# MODUL_LCD_V100.net
KiCad netlist of a schematic drawn in EAGLE
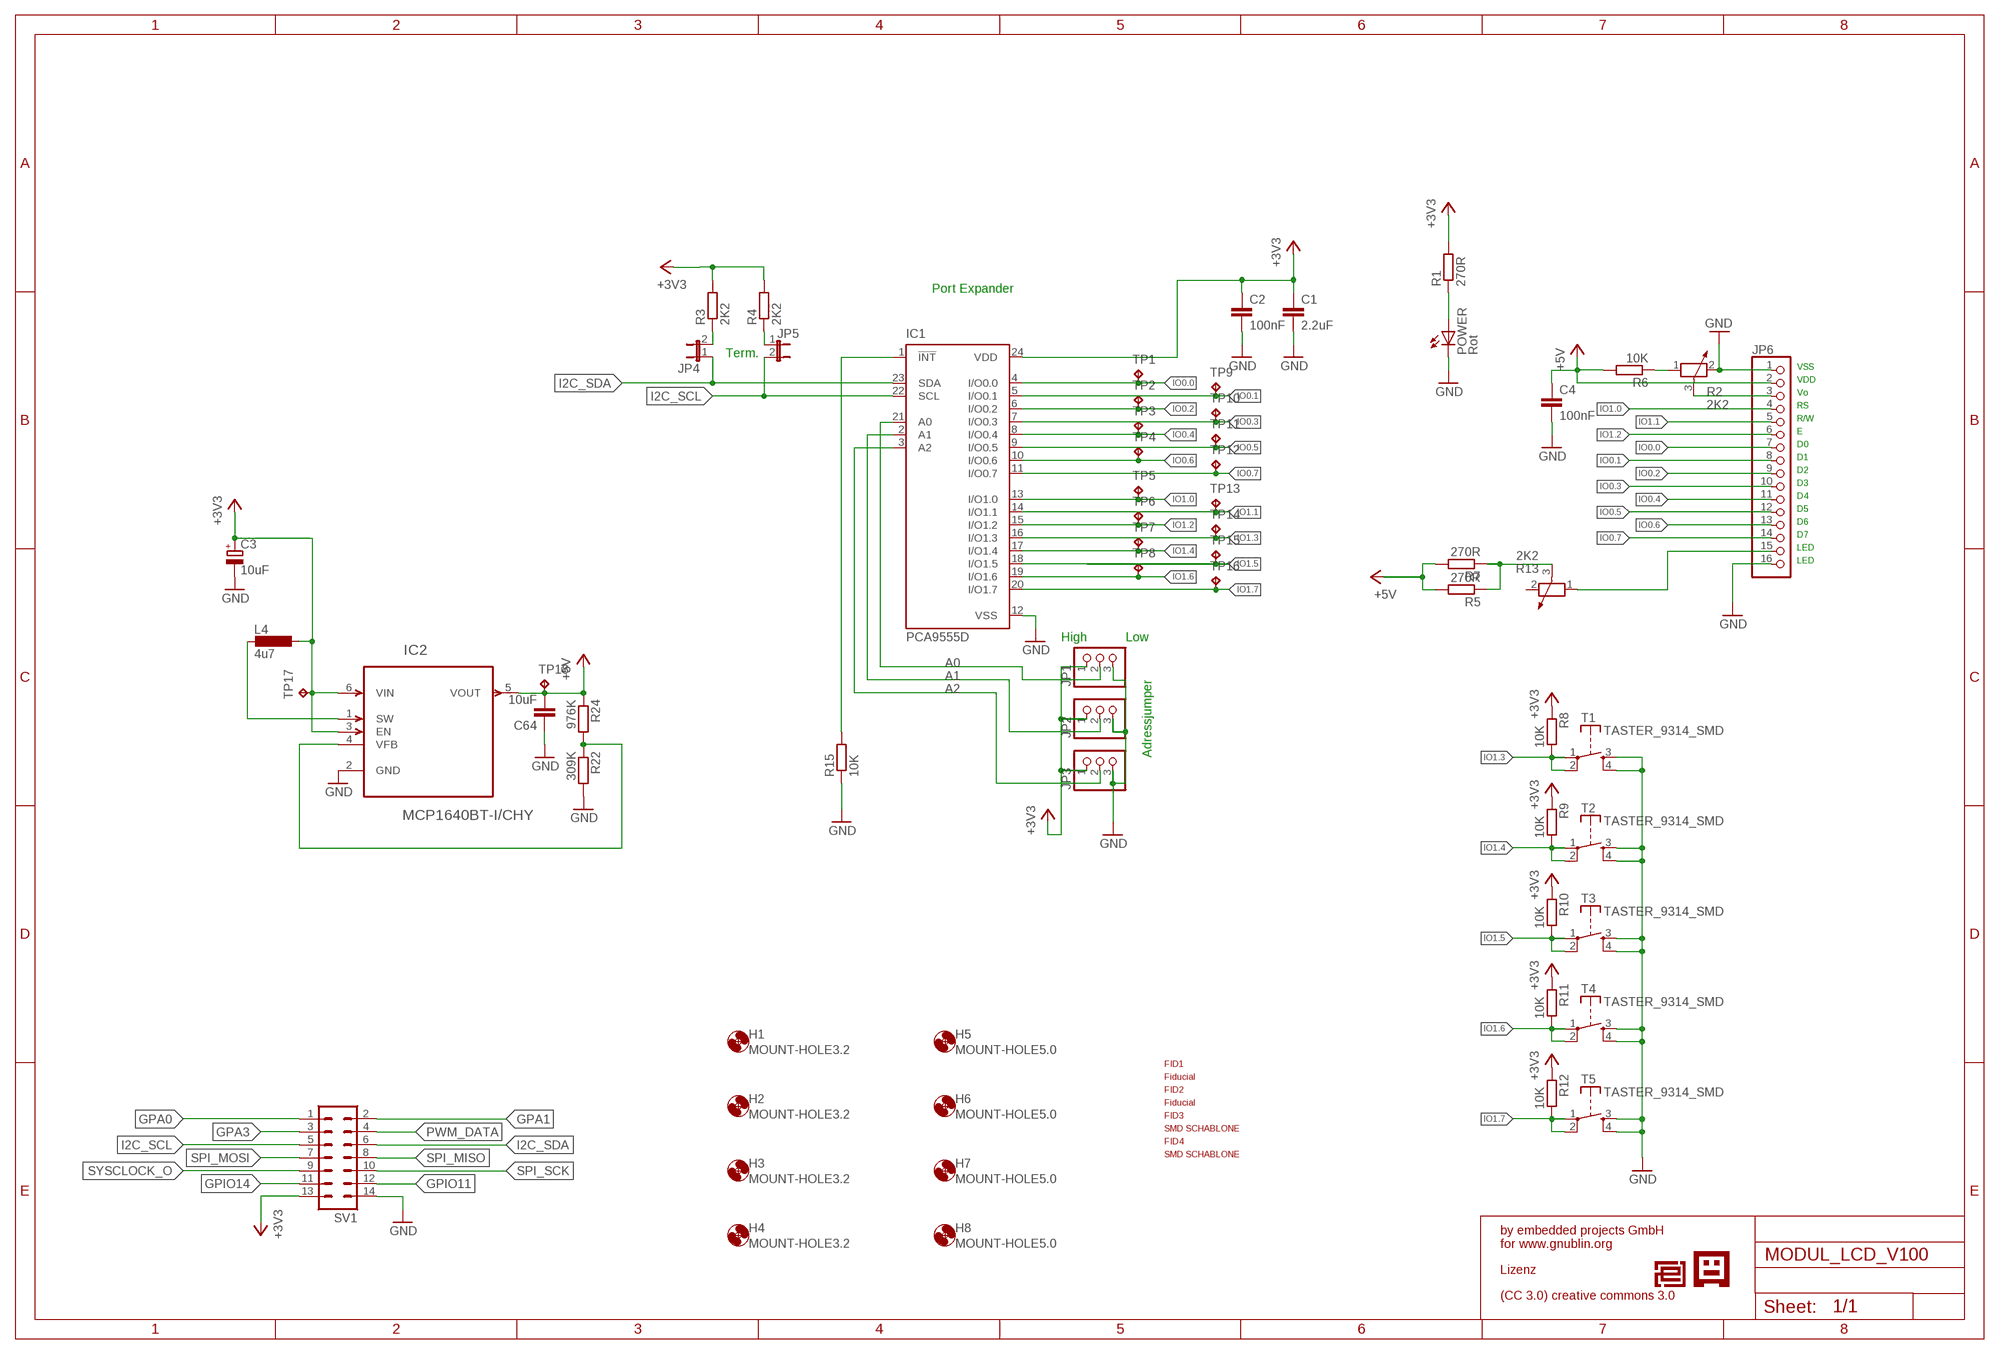
[diagram p0: schematic, sheet 1]

(export (version "E")
  (design (tool "Eeschema 10.0.6"))
  (components
    (comp (ref "C1")
      (value "2.2uF")
      (footprint "eagle-import:C0805")
      (libsource (lib "eagle-import") (part "C-EUC0805"))
    )
    (comp (ref "C2")
      (value "100nF")
      (footprint "eagle-import:C0805")
      (libsource (lib "eagle-import") (part "C-EUC0805"))
    )
    (comp (ref "C3")
      (value "10uF")
      (footprint "eagle-import:SMC_D")
      (libsource (lib "eagle-import") (part "CPOL-EUSMCD"))
    )
    (comp (ref "C4")
      (value "100nF")
      (footprint "eagle-import:C0805")
      (libsource (lib "eagle-import") (part "C-EUC0805"))
    )
    (comp (ref "C64")
      (value "10uF")
      (footprint "eagle-import:C0805")
      (libsource (lib "eagle-import") (part "C-EUC0805"))
    )
    (comp (ref "FID1")
      (value "PASSERMARKEN_FIDUCIAL")
      (footprint "eagle-import:PASSERMARKEN_FIDUCIAL")
      (libsource (lib "eagle-import") (part "PASSERMARKEN_FIDUCIAL"))
    )
    (comp (ref "FID2")
      (value "PASSERMARKEN_FIDUCIAL")
      (footprint "eagle-import:PASSERMARKEN_FIDUCIAL")
      (libsource (lib "eagle-import") (part "PASSERMARKEN_FIDUCIAL"))
    )
    (comp (ref "FID3")
      (value "PASSERMARKEN_FIDUCIAL")
      (footprint "eagle-import:PASSERMARKEN_FIDUCIAL")
      (libsource (lib "eagle-import") (part "SMDSCHABLONE_PASSERMARKEN_FIDUCIAL"))
    )
    (comp (ref "FID4")
      (value "PASSERMARKEN_FIDUCIAL")
      (footprint "eagle-import:PASSERMARKEN_FIDUCIAL")
      (libsource (lib "eagle-import") (part "SMDSCHABLONE_PASSERMARKEN_FIDUCIAL"))
    )
    (comp (ref "H1")
      (value "MOUNT-HOLE3.2")
      (footprint "eagle-import:3,2")
      (libsource (lib "eagle-import") (part "MOUNT-HOLE3.2"))
    )
    (comp (ref "H2")
      (value "MOUNT-HOLE3.2")
      (footprint "eagle-import:3,2")
      (libsource (lib "eagle-import") (part "MOUNT-HOLE3.2"))
    )
    (comp (ref "H3")
      (value "MOUNT-HOLE3.2")
      (footprint "eagle-import:3,2")
      (libsource (lib "eagle-import") (part "MOUNT-HOLE3.2"))
    )
    (comp (ref "H4")
      (value "MOUNT-HOLE3.2")
      (footprint "eagle-import:3,2")
      (libsource (lib "eagle-import") (part "MOUNT-HOLE3.2"))
    )
    (comp (ref "H5")
      (value "MOUNT-HOLE5.0")
      (footprint "eagle-import:5,0")
      (libsource (lib "eagle-import") (part "MOUNT-HOLE5.0"))
    )
    (comp (ref "H6")
      (value "MOUNT-HOLE5.0")
      (footprint "eagle-import:5,0")
      (libsource (lib "eagle-import") (part "MOUNT-HOLE5.0"))
    )
    (comp (ref "H7")
      (value "MOUNT-HOLE5.0")
      (footprint "eagle-import:5,0")
      (libsource (lib "eagle-import") (part "MOUNT-HOLE5.0"))
    )
    (comp (ref "H8")
      (value "MOUNT-HOLE5.0")
      (footprint "eagle-import:5,0")
      (libsource (lib "eagle-import") (part "MOUNT-HOLE5.0"))
    )
    (comp (ref "IC1")
      (value "PCA9555D")
      (footprint "eagle-import:SO24")
      (fields (field (name "MPN") "PCA9555DW") (field (name "OC_FARNELL") "8906076"))
      (libsource (lib "eagle-import") (part "PCA9555D"))
    )
    (comp (ref "IC2")
      (value "MCP1640BT-I/CHY")
      (footprint "eagle-import:SOT95P270X145-6N")
      (libsource (lib "eagle-import") (part "MCP1640BT-I/CHY"))
    )
    (comp (ref "JP1")
      (value "PINHD-1X3")
      (footprint "eagle-import:1X03")
      (libsource (lib "eagle-import") (part "PINHD-1X3"))
    )
    (comp (ref "JP2")
      (value "PINHD-1X3")
      (footprint "eagle-import:1X03")
      (libsource (lib "eagle-import") (part "PINHD-1X3"))
    )
    (comp (ref "JP3")
      (value "PINHD-1X3")
      (footprint "eagle-import:1X03")
      (libsource (lib "eagle-import") (part "PINHD-1X3"))
    )
    (comp (ref "JP4")
      (value "JP1E")
      (footprint "eagle-import:JP1")
      (libsource (lib "eagle-import") (part "JP1E"))
    )
    (comp (ref "JP5")
      (value "JP1E")
      (footprint "eagle-import:JP1")
      (libsource (lib "eagle-import") (part "JP1E"))
    )
    (comp (ref "JP6")
      (value "PINHD-1X16")
      (footprint "eagle-import:1X16")
      (libsource (lib "eagle-import") (part "PINHD-1X16"))
    )
    (comp (ref "L4")
      (value "4u7")
      (footprint "eagle-import:PSU3014")
      (libsource (lib "eagle-import") (part "PSU3014"))
    )
    (comp (ref "POWER")
      (value "Rot")
      (footprint "eagle-import:CHIP-LED0805")
      (libsource (lib "eagle-import") (part "LEDCHIP-LED0805"))
    )
    (comp (ref "R1")
      (value "270R")
      (footprint "eagle-import:R0805")
      (libsource (lib "eagle-import") (part "R-EU_R0805"))
    )
    (comp (ref "R2")
      (value "2K2")
      (footprint "eagle-import:PT-10")
      (libsource (lib "eagle-import") (part "POTENTIOMETER_PT-10"))
    )
    (comp (ref "R3")
      (value "2K2")
      (footprint "eagle-import:R0805")
      (libsource (lib "eagle-import") (part "R-EU_R0805"))
    )
    (comp (ref "R4")
      (value "2K2")
      (footprint "eagle-import:R0805")
      (libsource (lib "eagle-import") (part "R-EU_R0805"))
    )
    (comp (ref "R5")
      (value "270R")
      (footprint "eagle-import:R0805")
      (libsource (lib "eagle-import") (part "R-EU_R0805"))
    )
    (comp (ref "R6")
      (value "10K")
      (footprint "eagle-import:R0805")
      (libsource (lib "eagle-import") (part "R-EU_R0805"))
    )
    (comp (ref "R7")
      (value "270R")
      (footprint "eagle-import:R0805")
      (libsource (lib "eagle-import") (part "R-EU_R0805"))
    )
    (comp (ref "R8")
      (value "10K")
      (footprint "eagle-import:R0805")
      (libsource (lib "eagle-import") (part "R-EU_R0805"))
    )
    (comp (ref "R9")
      (value "10K")
      (footprint "eagle-import:R0805")
      (libsource (lib "eagle-import") (part "R-EU_R0805"))
    )
    (comp (ref "R10")
      (value "10K")
      (footprint "eagle-import:R0805")
      (libsource (lib "eagle-import") (part "R-EU_R0805"))
    )
    (comp (ref "R11")
      (value "10K")
      (footprint "eagle-import:R0805")
      (libsource (lib "eagle-import") (part "R-EU_R0805"))
    )
    (comp (ref "R12")
      (value "10K")
      (footprint "eagle-import:R0805")
      (libsource (lib "eagle-import") (part "R-EU_R0805"))
    )
    (comp (ref "R13")
      (value "2K2")
      (footprint "eagle-import:PT-10")
      (libsource (lib "eagle-import") (part "POTENTIOMETER_PT-10"))
    )
    (comp (ref "R15")
      (value "10K")
      (footprint "eagle-import:R0805")
      (libsource (lib "eagle-import") (part "R-EU_R0805"))
    )
    (comp (ref "R22")
      (value "309K")
      (footprint "eagle-import:R0805")
      (libsource (lib "eagle-import") (part "R-EU_R0805"))
    )
    (comp (ref "R24")
      (value "976K")
      (footprint "eagle-import:R0805")
      (libsource (lib "eagle-import") (part "R-EU_R0805"))
    )
    (comp (ref "SV1")
      (value "ML14")
      (footprint "eagle-import:ML14")
      (libsource (lib "eagle-import") (part "ML14"))
    )
    (comp (ref "T1")
      (value "TASTER_9314_SMD")
      (footprint "eagle-import:TASTER-9314_SMD")
      (libsource (lib "eagle-import") (part "TASTER_9314_SMD"))
    )
    (comp (ref "T2")
      (value "TASTER_9314_SMD")
      (footprint "eagle-import:TASTER-9314_SMD")
      (libsource (lib "eagle-import") (part "TASTER_9314_SMD"))
    )
    (comp (ref "T3")
      (value "TASTER_9314_SMD")
      (footprint "eagle-import:TASTER-9314_SMD")
      (libsource (lib "eagle-import") (part "TASTER_9314_SMD"))
    )
    (comp (ref "T4")
      (value "TASTER_9314_SMD")
      (footprint "eagle-import:TASTER-9314_SMD")
      (libsource (lib "eagle-import") (part "TASTER_9314_SMD"))
    )
    (comp (ref "T5")
      (value "TASTER_9314_SMD")
      (footprint "eagle-import:TASTER-9314_SMD")
      (libsource (lib "eagle-import") (part "TASTER_9314_SMD"))
    )
    (comp (ref "TP1")
      (value "TPB1,27")
      (footprint "eagle-import:B1,27")
      (libsource (lib "eagle-import") (part "TPB1,27"))
    )
    (comp (ref "TP2")
      (value "TPB1,27")
      (footprint "eagle-import:B1,27")
      (libsource (lib "eagle-import") (part "TPB1,27"))
    )
    (comp (ref "TP3")
      (value "TPB1,27")
      (footprint "eagle-import:B1,27")
      (libsource (lib "eagle-import") (part "TPB1,27"))
    )
    (comp (ref "TP4")
      (value "TPB1,27")
      (footprint "eagle-import:B1,27")
      (libsource (lib "eagle-import") (part "TPB1,27"))
    )
    (comp (ref "TP5")
      (value "TPB1,27")
      (footprint "eagle-import:B1,27")
      (libsource (lib "eagle-import") (part "TPB1,27"))
    )
    (comp (ref "TP6")
      (value "TPB1,27")
      (footprint "eagle-import:B1,27")
      (libsource (lib "eagle-import") (part "TPB1,27"))
    )
    (comp (ref "TP7")
      (value "TPB1,27")
      (footprint "eagle-import:B1,27")
      (libsource (lib "eagle-import") (part "TPB1,27"))
    )
    (comp (ref "TP8")
      (value "TPB1,27")
      (footprint "eagle-import:B1,27")
      (libsource (lib "eagle-import") (part "TPB1,27"))
    )
    (comp (ref "TP9")
      (value "TPB1,27")
      (footprint "eagle-import:B1,27")
      (libsource (lib "eagle-import") (part "TPB1,27"))
    )
    (comp (ref "TP10")
      (value "TPB1,27")
      (footprint "eagle-import:B1,27")
      (libsource (lib "eagle-import") (part "TPB1,27"))
    )
    (comp (ref "TP11")
      (value "TPB1,27")
      (footprint "eagle-import:B1,27")
      (libsource (lib "eagle-import") (part "TPB1,27"))
    )
    (comp (ref "TP12")
      (value "TPB1,27")
      (footprint "eagle-import:B1,27")
      (libsource (lib "eagle-import") (part "TPB1,27"))
    )
    (comp (ref "TP13")
      (value "TPB1,27")
      (footprint "eagle-import:B1,27")
      (libsource (lib "eagle-import") (part "TPB1,27"))
    )
    (comp (ref "TP14")
      (value "TPB1,27")
      (footprint "eagle-import:B1,27")
      (libsource (lib "eagle-import") (part "TPB1,27"))
    )
    (comp (ref "TP15")
      (value "TPB1,27")
      (footprint "eagle-import:B1,27")
      (libsource (lib "eagle-import") (part "TPB1,27"))
    )
    (comp (ref "TP16")
      (value "TPB1,27")
      (footprint "eagle-import:B1,27")
      (libsource (lib "eagle-import") (part "TPB1,27"))
    )
    (comp (ref "TP17")
      (value "TPB1,27")
      (footprint "eagle-import:B1,27")
      (libsource (lib "eagle-import") (part "TPB1,27"))
    )
    (comp (ref "TP18")
      (value "TPB1,27")
      (footprint "eagle-import:B1,27")
      (libsource (lib "eagle-import") (part "TPB1,27"))
    )
    (comp (ref "U$1")
      (value "EPLOGOSIEB")
      (footprint "eagle-import:EPLOGOSIEBDRUCK")
      (libsource (lib "eagle-import") (part "EPLOGOSIEB"))
    )
    (comp (ref "U$2")
      (value "GNUBLINLOGOSIEB")
      (footprint "eagle-import:GNUSIEBDRUCK")
      (libsource (lib "eagle-import") (part "GNUBLINLOGOSIEB"))
    )
  )
  (nets
    (net (code "1") (name "+3V3") (class "Default")
      (node (ref "C1") (pin "1") (pinfunction "1_1") (pintype "passive"))
      (node (ref "C2") (pin "1") (pinfunction "1_1") (pintype "passive"))
      (node (ref "C3") (pin "+") (pinfunction "+_+") (pintype "passive"))
      (node (ref "IC1") (pin "24") (pinfunction "VDD_24") (pintype "power_in"))
      (node (ref "IC2") (pin "3") (pinfunction "EN_3") (pintype "input"))
      (node (ref "IC2") (pin "6") (pinfunction "VIN_6") (pintype "input"))
      (node (ref "JP1") (pin "1") (pinfunction "1_1") (pintype "passive"))
      (node (ref "JP2") (pin "1") (pinfunction "1_1") (pintype "passive"))
      (node (ref "JP3") (pin "1") (pinfunction "1_1") (pintype "passive"))
      (node (ref "L4") (pin "2") (pinfunction "2_2") (pintype "passive"))
      (node (ref "R1") (pin "2") (pinfunction "2_2") (pintype "passive"))
      (node (ref "R10") (pin "1") (pinfunction "1_1") (pintype "passive"))
      (node (ref "R11") (pin "1") (pinfunction "1_1") (pintype "passive"))
      (node (ref "R12") (pin "1") (pinfunction "1_1") (pintype "passive"))
      (node (ref "R3") (pin "2") (pinfunction "2_2") (pintype "passive"))
      (node (ref "R4") (pin "2") (pinfunction "2_2") (pintype "passive"))
      (node (ref "R8") (pin "1") (pinfunction "1_1") (pintype "passive"))
      (node (ref "R9") (pin "1") (pinfunction "1_1") (pintype "passive"))
      (node (ref "SV1") (pin "13") (pinfunction "13_13") (pintype "passive"))
      (node (ref "TP17") (pin "TP") (pinfunction "TP_TP") (pintype "input"))
    )
    (net (code "2") (name "+5V") (class "Default")
      (node (ref "C4") (pin "1") (pinfunction "1_1") (pintype "passive"))
      (node (ref "C64") (pin "2") (pinfunction "2_2") (pintype "passive"))
      (node (ref "IC2") (pin "5") (pinfunction "VOUT_5") (pintype "output"))
      (node (ref "JP6") (pin "2") (pinfunction "2_2") (pintype "passive"))
      (node (ref "R24") (pin "1") (pinfunction "1_1") (pintype "passive"))
      (node (ref "R5") (pin "2") (pinfunction "2_2") (pintype "passive"))
      (node (ref "R6") (pin "2") (pinfunction "2_2") (pintype "passive"))
      (node (ref "R7") (pin "2") (pinfunction "2_2") (pintype "passive"))
      (node (ref "TP18") (pin "TP") (pinfunction "TP_TP") (pintype "input"))
    )
    (net (code "3") (name "/A0") (class "Default")
      (node (ref "IC1") (pin "21") (pinfunction "A0_21") (pintype "input"))
      (node (ref "JP1") (pin "2") (pinfunction "2_2") (pintype "passive"))
    )
    (net (code "4") (name "/A1") (class "Default")
      (node (ref "IC1") (pin "2") (pinfunction "A1_2") (pintype "input"))
      (node (ref "JP2") (pin "2") (pinfunction "2_2") (pintype "passive"))
    )
    (net (code "5") (name "/A2") (class "Default")
      (node (ref "IC1") (pin "3") (pinfunction "A2_3") (pintype "input"))
      (node (ref "JP3") (pin "2") (pinfunction "2_2") (pintype "passive"))
    )
    (net (code "6") (name "GND") (class "Default")
      (node (ref "C1") (pin "2") (pinfunction "2_2") (pintype "passive"))
      (node (ref "C2") (pin "2") (pinfunction "2_2") (pintype "passive"))
      (node (ref "C3") (pin "-") (pinfunction "-_-") (pintype "passive"))
      (node (ref "C4") (pin "2") (pinfunction "2_2") (pintype "passive"))
      (node (ref "C64") (pin "1") (pinfunction "1_1") (pintype "passive"))
      (node (ref "IC1") (pin "12") (pinfunction "VSS_12") (pintype "power_in"))
      (node (ref "IC2") (pin "2") (pinfunction "GND_2") (pintype "passive"))
      (node (ref "JP1") (pin "3") (pinfunction "3_3") (pintype "passive"))
      (node (ref "JP2") (pin "3") (pinfunction "3_3") (pintype "passive"))
      (node (ref "JP3") (pin "3") (pinfunction "3_3") (pintype "passive"))
      (node (ref "JP6") (pin "1") (pinfunction "1_1") (pintype "passive"))
      (node (ref "JP6") (pin "16") (pinfunction "16_16") (pintype "passive"))
      (node (ref "POWER") (pin "C") (pinfunction "C_C") (pintype "passive"))
      (node (ref "R15") (pin "1") (pinfunction "1_1") (pintype "passive"))
      (node (ref "R2") (pin "2") (pinfunction "2_2") (pintype "passive"))
      (node (ref "R22") (pin "2") (pinfunction "2_2") (pintype "passive"))
      (node (ref "SV1") (pin "14") (pinfunction "14_14") (pintype "passive"))
      (node (ref "T1") (pin "3") (pinfunction "S_3") (pintype "passive"))
      (node (ref "T1") (pin "4") (pinfunction "S_4") (pintype "passive"))
      (node (ref "T2") (pin "3") (pinfunction "S_3") (pintype "passive"))
      (node (ref "T2") (pin "4") (pinfunction "S_4") (pintype "passive"))
      (node (ref "T3") (pin "3") (pinfunction "S_3") (pintype "passive"))
      (node (ref "T3") (pin "4") (pinfunction "S_4") (pintype "passive"))
      (node (ref "T4") (pin "3") (pinfunction "S_3") (pintype "passive"))
      (node (ref "T4") (pin "4") (pinfunction "S_4") (pintype "passive"))
      (node (ref "T5") (pin "3") (pinfunction "S_3") (pintype "passive"))
      (node (ref "T5") (pin "4") (pinfunction "S_4") (pintype "passive"))
    )
    (net (code "7") (name "GPA0") (class "Default")
      (node (ref "SV1") (pin "1") (pinfunction "1_1") (pintype "passive"))
    )
    (net (code "8") (name "GPA1") (class "Default")
      (node (ref "SV1") (pin "2") (pinfunction "2_2") (pintype "passive"))
    )
    (net (code "9") (name "GPA3") (class "Default")
      (node (ref "SV1") (pin "3") (pinfunction "3_3") (pintype "passive"))
    )
    (net (code "10") (name "GPIO11") (class "Default")
      (node (ref "SV1") (pin "12") (pinfunction "12_12") (pintype "passive"))
    )
    (net (code "11") (name "GPIO14") (class "Default")
      (node (ref "SV1") (pin "11") (pinfunction "11_11") (pintype "passive"))
    )
    (net (code "12") (name "I2C_SCL") (class "Default")
      (node (ref "IC1") (pin "22") (pinfunction "SCL_22") (pintype "input"))
      (node (ref "JP5") (pin "2") (pinfunction "2_2") (pintype "passive"))
      (node (ref "SV1") (pin "5") (pinfunction "5_5") (pintype "passive"))
    )
    (net (code "13") (name "I2C_SDA") (class "Default")
      (node (ref "IC1") (pin "23") (pinfunction "SDA_23") (pintype "bidirectional"))
      (node (ref "JP4") (pin "1") (pinfunction "1_1") (pintype "passive"))
      (node (ref "SV1") (pin "6") (pinfunction "6_6") (pintype "passive"))
    )
    (net (code "14") (name "IO0.0") (class "Default")
      (node (ref "IC1") (pin "4") (pinfunction "I/O0.0_4") (pintype "bidirectional"))
      (node (ref "JP6") (pin "7") (pinfunction "7_7") (pintype "passive"))
      (node (ref "TP1") (pin "TP") (pinfunction "TP_TP") (pintype "input"))
    )
    (net (code "15") (name "IO0.1") (class "Default")
      (node (ref "IC1") (pin "5") (pinfunction "I/O0.1_5") (pintype "bidirectional"))
      (node (ref "JP6") (pin "8") (pinfunction "8_8") (pintype "passive"))
      (node (ref "TP9") (pin "TP") (pinfunction "TP_TP") (pintype "input"))
    )
    (net (code "16") (name "IO0.2") (class "Default")
      (node (ref "IC1") (pin "6") (pinfunction "I/O0.2_6") (pintype "bidirectional"))
      (node (ref "JP6") (pin "9") (pinfunction "9_9") (pintype "passive"))
      (node (ref "TP2") (pin "TP") (pinfunction "TP_TP") (pintype "input"))
    )
    (net (code "17") (name "IO0.3") (class "Default")
      (node (ref "IC1") (pin "7") (pinfunction "I/O0.3_7") (pintype "bidirectional"))
      (node (ref "JP6") (pin "10") (pinfunction "10_10") (pintype "passive"))
      (node (ref "TP10") (pin "TP") (pinfunction "TP_TP") (pintype "input"))
    )
    (net (code "18") (name "IO0.4") (class "Default")
      (node (ref "IC1") (pin "8") (pinfunction "I/O0.4_8") (pintype "bidirectional"))
      (node (ref "JP6") (pin "11") (pinfunction "11_11") (pintype "passive"))
      (node (ref "TP3") (pin "TP") (pinfunction "TP_TP") (pintype "input"))
    )
    (net (code "19") (name "IO0.5") (class "Default")
      (node (ref "IC1") (pin "9") (pinfunction "I/O0.5_9") (pintype "bidirectional"))
      (node (ref "JP6") (pin "12") (pinfunction "12_12") (pintype "passive"))
      (node (ref "TP11") (pin "TP") (pinfunction "TP_TP") (pintype "input"))
    )
    (net (code "20") (name "IO0.6") (class "Default")
      (node (ref "IC1") (pin "10") (pinfunction "I/O0.6_10") (pintype "bidirectional"))
      (node (ref "JP6") (pin "13") (pinfunction "13_13") (pintype "passive"))
      (node (ref "TP4") (pin "TP") (pinfunction "TP_TP") (pintype "input"))
    )
    (net (code "21") (name "IO0.7") (class "Default")
      (node (ref "IC1") (pin "11") (pinfunction "I/O0.7_11") (pintype "bidirectional"))
      (node (ref "JP6") (pin "14") (pinfunction "14_14") (pintype "passive"))
      (node (ref "TP12") (pin "TP") (pinfunction "TP_TP") (pintype "input"))
    )
    (net (code "22") (name "IO1.0") (class "Default")
      (node (ref "IC1") (pin "13") (pinfunction "I/O1.0_13") (pintype "bidirectional"))
      (node (ref "JP6") (pin "4") (pinfunction "4_4") (pintype "passive"))
      (node (ref "TP5") (pin "TP") (pinfunction "TP_TP") (pintype "input"))
    )
    (net (code "23") (name "IO1.1") (class "Default")
      (node (ref "IC1") (pin "14") (pinfunction "I/O1.1_14") (pintype "bidirectional"))
      (node (ref "JP6") (pin "5") (pinfunction "5_5") (pintype "passive"))
      (node (ref "TP13") (pin "TP") (pinfunction "TP_TP") (pintype "input"))
    )
    (net (code "24") (name "IO1.2") (class "Default")
      (node (ref "IC1") (pin "15") (pinfunction "I/O1.2_15") (pintype "bidirectional"))
      (node (ref "JP6") (pin "6") (pinfunction "6_6") (pintype "passive"))
      (node (ref "TP6") (pin "TP") (pinfunction "TP_TP") (pintype "input"))
    )
    (net (code "25") (name "IO1.3") (class "Default")
      (node (ref "IC1") (pin "16") (pinfunction "I/O1.3_16") (pintype "bidirectional"))
      (node (ref "R8") (pin "2") (pinfunction "2_2") (pintype "passive"))
      (node (ref "T1") (pin "1") (pinfunction "P_1") (pintype "passive"))
      (node (ref "T1") (pin "2") (pinfunction "P_2") (pintype "passive"))
      (node (ref "TP14") (pin "TP") (pinfunction "TP_TP") (pintype "input"))
    )
    (net (code "26") (name "IO1.4") (class "Default")
      (node (ref "IC1") (pin "17") (pinfunction "I/O1.4_17") (pintype "bidirectional"))
      (node (ref "R9") (pin "2") (pinfunction "2_2") (pintype "passive"))
      (node (ref "T2") (pin "1") (pinfunction "P_1") (pintype "passive"))
      (node (ref "T2") (pin "2") (pinfunction "P_2") (pintype "passive"))
      (node (ref "TP7") (pin "TP") (pinfunction "TP_TP") (pintype "input"))
    )
    (net (code "27") (name "IO1.5") (class "Default")
      (node (ref "IC1") (pin "18") (pinfunction "I/O1.5_18") (pintype "bidirectional"))
      (node (ref "R10") (pin "2") (pinfunction "2_2") (pintype "passive"))
      (node (ref "T3") (pin "1") (pinfunction "P_1") (pintype "passive"))
      (node (ref "T3") (pin "2") (pinfunction "P_2") (pintype "passive"))
      (node (ref "TP15") (pin "TP") (pinfunction "TP_TP") (pintype "input"))
    )
    (net (code "28") (name "IO1.6") (class "Default")
      (node (ref "IC1") (pin "19") (pinfunction "I/O1.6_19") (pintype "bidirectional"))
      (node (ref "R11") (pin "2") (pinfunction "2_2") (pintype "passive"))
      (node (ref "T4") (pin "1") (pinfunction "P_1") (pintype "passive"))
      (node (ref "T4") (pin "2") (pinfunction "P_2") (pintype "passive"))
      (node (ref "TP8") (pin "TP") (pinfunction "TP_TP") (pintype "input"))
    )
    (net (code "29") (name "IO1.7") (class "Default")
      (node (ref "IC1") (pin "20") (pinfunction "I/O1.7_20") (pintype "bidirectional"))
      (node (ref "R12") (pin "2") (pinfunction "2_2") (pintype "passive"))
      (node (ref "T5") (pin "1") (pinfunction "P_1") (pintype "passive"))
      (node (ref "T5") (pin "2") (pinfunction "P_2") (pintype "passive"))
      (node (ref "TP16") (pin "TP") (pinfunction "TP_TP") (pintype "input"))
    )
    (net (code "30") (name "Net-(IC1-~{INT})") (class "Default")
      (node (ref "IC1") (pin "1") (pinfunction "~{INT}_1") (pintype "output"))
      (node (ref "R15") (pin "2") (pinfunction "2_2") (pintype "passive"))
    )
    (net (code "31") (name "Net-(IC2-SW)") (class "Default")
      (node (ref "IC2") (pin "1") (pinfunction "SW_1") (pintype "input"))
      (node (ref "L4") (pin "1") (pinfunction "1_1") (pintype "passive"))
    )
    (net (code "32") (name "Net-(IC2-VFB)") (class "Default")
      (node (ref "IC2") (pin "4") (pinfunction "VFB_4") (pintype "input"))
      (node (ref "R22") (pin "1") (pinfunction "1_1") (pintype "passive"))
      (node (ref "R24") (pin "2") (pinfunction "2_2") (pintype "passive"))
    )
    (net (code "33") (name "Net-(JP4-Pad2)") (class "Default")
      (node (ref "JP4") (pin "2") (pinfunction "2_2") (pintype "passive"))
      (node (ref "R3") (pin "1") (pinfunction "1_1") (pintype "passive"))
    )
    (net (code "34") (name "Net-(JP5-Pad1)") (class "Default")
      (node (ref "JP5") (pin "1") (pinfunction "1_1") (pintype "passive"))
      (node (ref "R4") (pin "1") (pinfunction "1_1") (pintype "passive"))
    )
    (net (code "35") (name "Net-(JP6-Pad3)") (class "Default")
      (node (ref "JP6") (pin "3") (pinfunction "3_3") (pintype "passive"))
      (node (ref "R2") (pin "3") (pinfunction "3_3") (pintype "passive"))
    )
    (net (code "36") (name "Net-(JP6-Pad15)") (class "Default")
      (node (ref "JP6") (pin "15") (pinfunction "15_15") (pintype "passive"))
      (node (ref "R13") (pin "1") (pinfunction "1_1") (pintype "passive"))
    )
    (net (code "37") (name "Net-(POWER-PadA)") (class "Default")
      (node (ref "POWER") (pin "A") (pinfunction "A_A") (pintype "passive"))
      (node (ref "R1") (pin "1") (pinfunction "1_1") (pintype "passive"))
    )
    (net (code "38") (name "Net-(R2-Pad1)") (class "Default")
      (node (ref "R2") (pin "1") (pinfunction "1_1") (pintype "passive"))
      (node (ref "R6") (pin "1") (pinfunction "1_1") (pintype "passive"))
    )
    (net (code "39") (name "Net-(R13-Pad3)") (class "Default")
      (node (ref "R13") (pin "3") (pinfunction "3_3") (pintype "passive"))
      (node (ref "R5") (pin "1") (pinfunction "1_1") (pintype "passive"))
      (node (ref "R7") (pin "1") (pinfunction "1_1") (pintype "passive"))
    )
    (net (code "40") (name "PWM_DATA") (class "Default")
      (node (ref "SV1") (pin "4") (pinfunction "4_4") (pintype "passive"))
    )
    (net (code "41") (name "SPI_MISO") (class "Default")
      (node (ref "SV1") (pin "8") (pinfunction "8_8") (pintype "passive"))
    )
    (net (code "42") (name "SPI_MOSI") (class "Default")
      (node (ref "SV1") (pin "7") (pinfunction "7_7") (pintype "passive"))
    )
    (net (code "43") (name "SPI_SCK") (class "Default")
      (node (ref "SV1") (pin "10") (pinfunction "10_10") (pintype "passive"))
    )
    (net (code "44") (name "SYSCLOCK_O") (class "Default")
      (node (ref "SV1") (pin "9") (pinfunction "9_9") (pintype "passive"))
    )
    (net (code "45") (name "unconnected-(R13-Pad2)") (class "Default")
      (node (ref "R13") (pin "2") (pinfunction "2_2") (pintype "passive"))
    )
  )
)
